# M697D.net
KiCad netlist of a schematic drawn in EAGLE
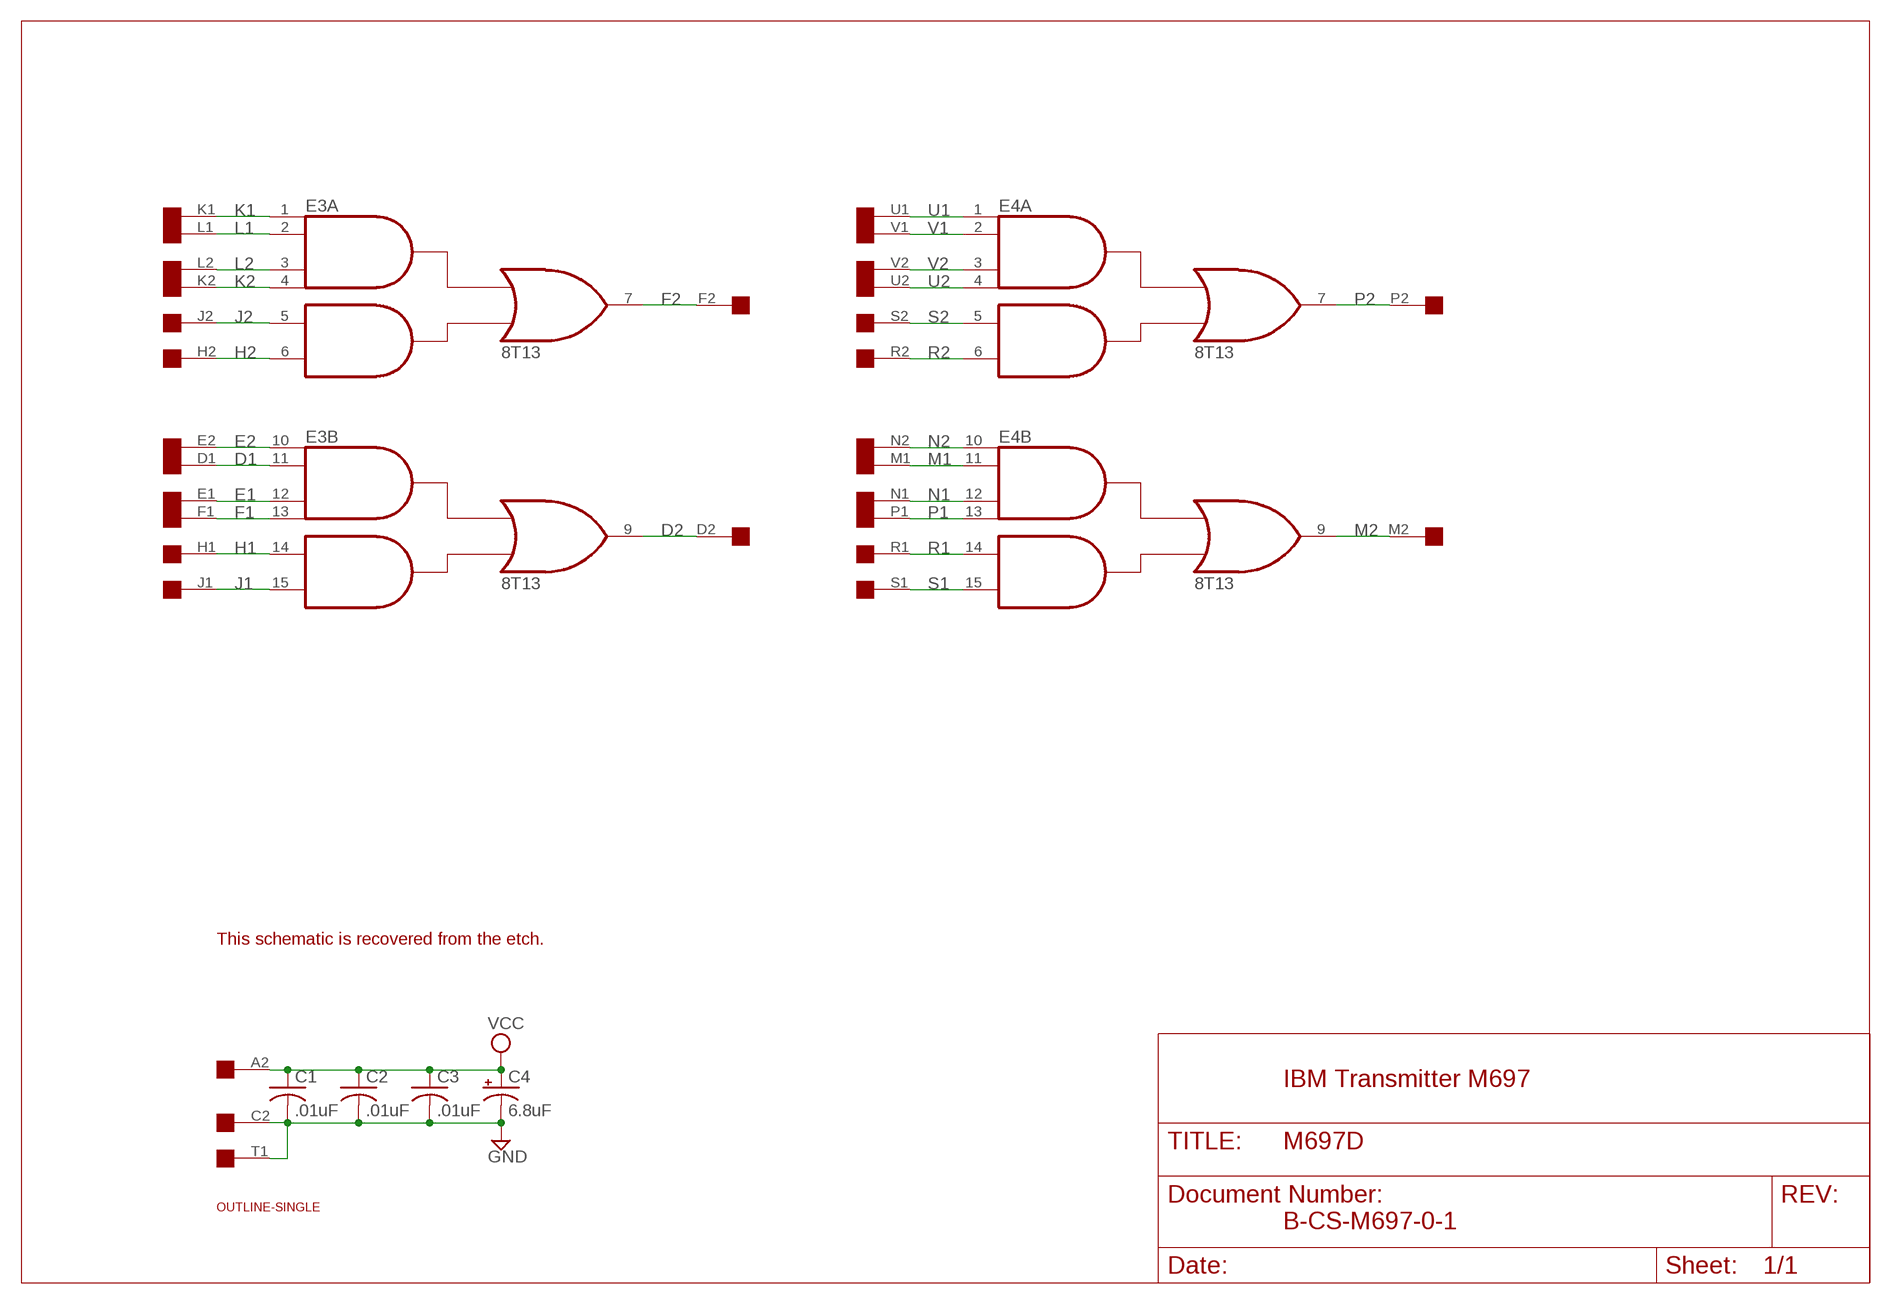
[diagram p0: schematic, sheet 1]

(export (version "E")
  (design (tool "Eeschema 10.0.6"))
  (components
    (comp (ref "C1")
      (value ".01uF")
      (footprint "eagle-import:C050-025X075")
      (libsource (lib "eagle-import") (part "C-US050-025X075"))
    )
    (comp (ref "C2")
      (value ".01uF")
      (footprint "eagle-import:C050-025X075")
      (libsource (lib "eagle-import") (part "C-US050-025X075"))
    )
    (comp (ref "C3")
      (value ".01uF")
      (footprint "eagle-import:C050-025X075")
      (libsource (lib "eagle-import") (part "C-US050-025X075"))
    )
    (comp (ref "C4")
      (value "6.8uF")
      (footprint "eagle-import:E12-8")
      (libsource (lib "eagle-import") (part "CPOL-USE20-8AXIAL"))
    )
    (comp (ref "E3")
      (value "8T13")
      (footprint "eagle-import:DIL16")
      (libsource (lib "eagle-import") (part "8T13"))
    )
    (comp (ref "E4")
      (value "8T13")
      (footprint "eagle-import:DIL16")
      (libsource (lib "eagle-import") (part "8T13"))
    )
    (comp (ref "U$2")
      (value "SINGLE")
      (footprint "eagle-import:EDGE-CON2")
      (libsource (lib "eagle-import") (part "SINGLE"))
    )
    (comp (ref "U$4")
      (value "OUTLINE-SINGLE")
      (footprint "eagle-import:SINGLE")
      (libsource (lib "eagle-import") (part "OUTLINE-SINGLE"))
    )
  )
  (nets
    (net (code "1") (name "/D1") (class "Default")
      (node (ref "E3") (pin "11") (pinfunction "A2_11") (pintype "input"))
      (node (ref "U$2") (pin "D1") (pinfunction "1_D1") (pintype "bidirectional"))
    )
    (net (code "2") (name "/D2") (class "Default")
      (node (ref "E3") (pin "9") (pinfunction "O_9") (pintype "output"))
      (node (ref "U$2") (pin "D2") (pinfunction "1_D2") (pintype "bidirectional"))
    )
    (net (code "3") (name "/E1") (class "Default")
      (node (ref "E3") (pin "12") (pinfunction "A3_12") (pintype "input"))
      (node (ref "U$2") (pin "E1") (pinfunction "1_E1") (pintype "bidirectional"))
    )
    (net (code "4") (name "/E2") (class "Default")
      (node (ref "E3") (pin "10") (pinfunction "A1_10") (pintype "input"))
      (node (ref "U$2") (pin "E2") (pinfunction "1_E2") (pintype "bidirectional"))
    )
    (net (code "5") (name "/F1") (class "Default")
      (node (ref "E3") (pin "13") (pinfunction "A4_13") (pintype "input"))
      (node (ref "U$2") (pin "F1") (pinfunction "1_F1") (pintype "bidirectional"))
    )
    (net (code "6") (name "/F2") (class "Default")
      (node (ref "E3") (pin "7") (pinfunction "O_7") (pintype "output"))
      (node (ref "U$2") (pin "F2") (pinfunction "1_F2") (pintype "bidirectional"))
    )
    (net (code "7") (name "/H1") (class "Default")
      (node (ref "E3") (pin "14") (pinfunction "B1_14") (pintype "input"))
      (node (ref "U$2") (pin "H1") (pinfunction "1_H1") (pintype "bidirectional"))
    )
    (net (code "8") (name "/H2") (class "Default")
      (node (ref "E3") (pin "6") (pinfunction "B2_6") (pintype "input"))
      (node (ref "U$2") (pin "H2") (pinfunction "1_H2") (pintype "bidirectional"))
    )
    (net (code "9") (name "/J1") (class "Default")
      (node (ref "E3") (pin "15") (pinfunction "B2_15") (pintype "input"))
      (node (ref "U$2") (pin "J1") (pinfunction "1_J1") (pintype "bidirectional"))
    )
    (net (code "10") (name "/J2") (class "Default")
      (node (ref "E3") (pin "5") (pinfunction "B1_5") (pintype "input"))
      (node (ref "U$2") (pin "J2") (pinfunction "1_J2") (pintype "bidirectional"))
    )
    (net (code "11") (name "/K1") (class "Default")
      (node (ref "E3") (pin "1") (pinfunction "A1_1") (pintype "input"))
      (node (ref "U$2") (pin "K1") (pinfunction "1_K1") (pintype "bidirectional"))
    )
    (net (code "12") (name "/K2") (class "Default")
      (node (ref "E3") (pin "4") (pinfunction "A4_4") (pintype "input"))
      (node (ref "U$2") (pin "K2") (pinfunction "1_K2") (pintype "bidirectional"))
    )
    (net (code "13") (name "/L1") (class "Default")
      (node (ref "E3") (pin "2") (pinfunction "A2_2") (pintype "input"))
      (node (ref "U$2") (pin "L1") (pinfunction "1_L1") (pintype "bidirectional"))
    )
    (net (code "14") (name "/L2") (class "Default")
      (node (ref "E3") (pin "3") (pinfunction "A3_3") (pintype "input"))
      (node (ref "U$2") (pin "L2") (pinfunction "1_L2") (pintype "bidirectional"))
    )
    (net (code "15") (name "/M1") (class "Default")
      (node (ref "E4") (pin "11") (pinfunction "A2_11") (pintype "input"))
      (node (ref "U$2") (pin "M1") (pinfunction "1_M1") (pintype "bidirectional"))
    )
    (net (code "16") (name "/M2") (class "Default")
      (node (ref "E4") (pin "9") (pinfunction "O_9") (pintype "output"))
      (node (ref "U$2") (pin "M2") (pinfunction "1_M2") (pintype "bidirectional"))
    )
    (net (code "17") (name "/N1") (class "Default")
      (node (ref "E4") (pin "12") (pinfunction "A3_12") (pintype "input"))
      (node (ref "U$2") (pin "N1") (pinfunction "1_N1") (pintype "bidirectional"))
    )
    (net (code "18") (name "/N2") (class "Default")
      (node (ref "E4") (pin "10") (pinfunction "A1_10") (pintype "input"))
      (node (ref "U$2") (pin "N2") (pinfunction "1_N2") (pintype "bidirectional"))
    )
    (net (code "19") (name "/P1") (class "Default")
      (node (ref "E4") (pin "13") (pinfunction "A4_13") (pintype "input"))
      (node (ref "U$2") (pin "P1") (pinfunction "1_P1") (pintype "bidirectional"))
    )
    (net (code "20") (name "/P2") (class "Default")
      (node (ref "E4") (pin "7") (pinfunction "O_7") (pintype "output"))
      (node (ref "U$2") (pin "P2") (pinfunction "1_P2") (pintype "bidirectional"))
    )
    (net (code "21") (name "/R1") (class "Default")
      (node (ref "E4") (pin "14") (pinfunction "B1_14") (pintype "input"))
      (node (ref "U$2") (pin "R1") (pinfunction "1_R1") (pintype "bidirectional"))
    )
    (net (code "22") (name "/R2") (class "Default")
      (node (ref "E4") (pin "6") (pinfunction "B2_6") (pintype "input"))
      (node (ref "U$2") (pin "R2") (pinfunction "1_R2") (pintype "bidirectional"))
    )
    (net (code "23") (name "/S1") (class "Default")
      (node (ref "E4") (pin "15") (pinfunction "B2_15") (pintype "input"))
      (node (ref "U$2") (pin "S1") (pinfunction "1_S1") (pintype "bidirectional"))
    )
    (net (code "24") (name "/S2") (class "Default")
      (node (ref "E4") (pin "5") (pinfunction "B1_5") (pintype "input"))
      (node (ref "U$2") (pin "S2") (pinfunction "1_S2") (pintype "bidirectional"))
    )
    (net (code "25") (name "/U1") (class "Default")
      (node (ref "E4") (pin "1") (pinfunction "A1_1") (pintype "input"))
      (node (ref "U$2") (pin "U1") (pinfunction "1_U1") (pintype "bidirectional"))
    )
    (net (code "26") (name "/U2") (class "Default")
      (node (ref "E4") (pin "4") (pinfunction "A4_4") (pintype "input"))
      (node (ref "U$2") (pin "U2") (pinfunction "1_U2") (pintype "bidirectional"))
    )
    (net (code "27") (name "/V1") (class "Default")
      (node (ref "E4") (pin "2") (pinfunction "A2_2") (pintype "input"))
      (node (ref "U$2") (pin "V1") (pinfunction "1_V1") (pintype "bidirectional"))
    )
    (net (code "28") (name "/V2") (class "Default")
      (node (ref "E4") (pin "3") (pinfunction "A3_3") (pintype "input"))
      (node (ref "U$2") (pin "V2") (pinfunction "1_V2") (pintype "bidirectional"))
    )
    (net (code "29") (name "GND") (class "Default")
      (node (ref "C1") (pin "2") (pinfunction "2_2") (pintype "passive"))
      (node (ref "C2") (pin "2") (pinfunction "2_2") (pintype "passive"))
      (node (ref "C3") (pin "2") (pinfunction "2_2") (pintype "passive"))
      (node (ref "C4") (pin "-") (pinfunction "-_-") (pintype "passive"))
      (node (ref "U$2") (pin "C2") (pinfunction "1_C2") (pintype "bidirectional"))
      (node (ref "U$2") (pin "T1") (pinfunction "1_T1") (pintype "bidirectional"))
    )
    (net (code "30") (name "VCC") (class "Default")
      (node (ref "C1") (pin "1") (pinfunction "1_1") (pintype "passive"))
      (node (ref "C2") (pin "1") (pinfunction "1_1") (pintype "passive"))
      (node (ref "C3") (pin "1") (pinfunction "1_1") (pintype "passive"))
      (node (ref "C4") (pin "+") (pinfunction "+_+") (pintype "passive"))
      (node (ref "U$2") (pin "A2") (pinfunction "1_A2") (pintype "bidirectional"))
    )
  )
)
